# SCH_Weighing-Scale_2024-05-28.net
KiCad netlist of a schematic drawn in EasyEDA
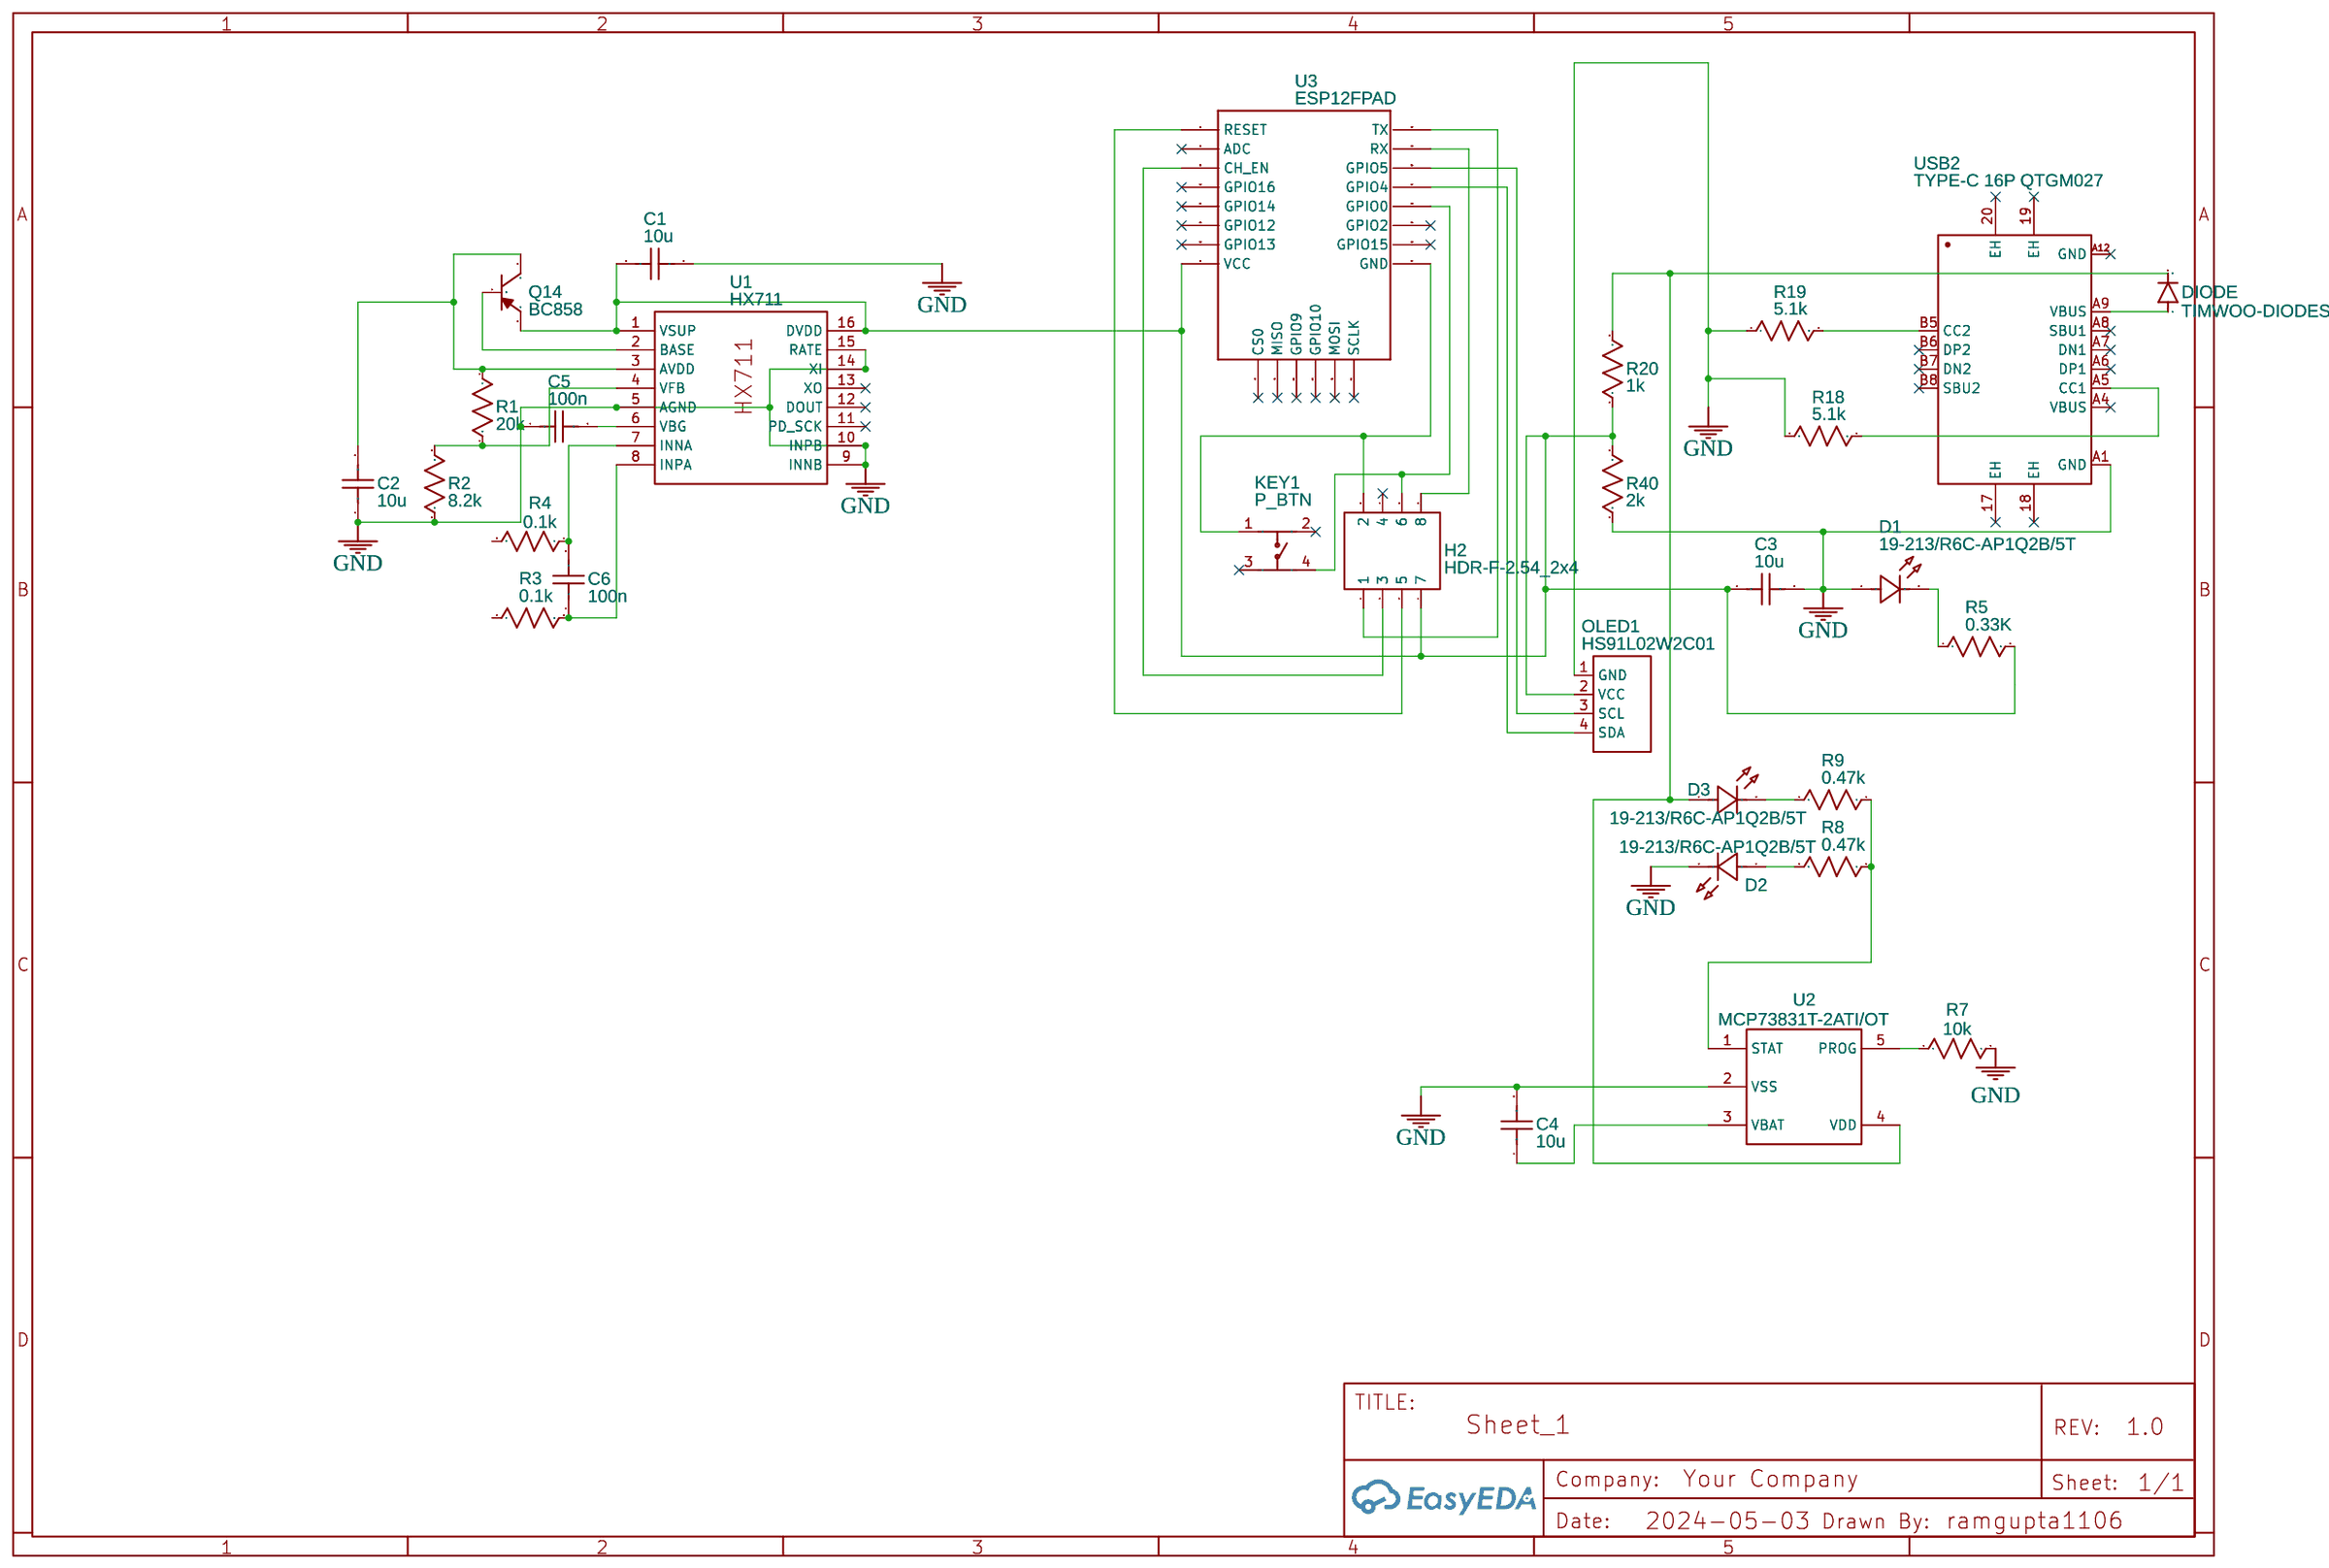
[diagram p0: schematic sheet]

(export (version "E")
  (design (tool "Eeschema 10.0.6"))
  (components
    (comp (ref "C1") (value "10u") (libsource (lib "") (part "C_0603_US_1")))
    (comp (ref "C2") (value "10u") (libsource (lib "") (part "C_0603_US")))
    (comp (ref "C3") (value "10u") (libsource (lib "") (part "C_0603_US_1")))
    (comp (ref "C4") (value "10u") (libsource (lib "") (part "C_0603_US")))
    (comp (ref "C5") (value "100n") (libsource (lib "") (part "C_0603_US_1")))
    (comp (ref "C6") (value "100n") (libsource (lib "") (part "C_0603_US")))
    (comp (ref "D1")
      (value "19-213/R6C-AP1Q2B/5T")
      (fields (field (name "Manufacturer") "EVERLIGHT(亿光)"))
      (libsource (lib "") (part "19-213/R6C-AP1Q2B/5T"))
    )
    (comp (ref "D2")
      (value "19-213/R6C-AP1Q2B/5T")
      (fields (field (name "Manufacturer") "EVERLIGHT(亿光)"))
      (libsource (lib "") (part "19-213/R6C-AP1Q2B/5T_1"))
    )
    (comp (ref "D3")
      (value "19-213/R6C-AP1Q2B/5T")
      (fields (field (name "Manufacturer") "EVERLIGHT(亿光)"))
      (libsource (lib "") (part "19-213/R6C-AP1Q2B/5T"))
    )
    (comp (ref "DIODE") (value "TIMWOO-DIODES_DIODEHV") (libsource (lib "") (part "TIMWOO-DIODES_DIODEHV")))
    (comp (ref "H2") (value "HDR-F-2.54_2x4") (libsource (lib "") (part "HDR-F-2.54_2x4")))
    (comp (ref "KEY1")
      (value "P_BTN")
      (fields (field (name "Manufacturer Part") "4pinTACTPCBTHTPushButton"))
      (libsource (lib "") (part "4PINTACTPCBTHTPUSHBUTTON"))
    )
    (comp (ref "OLED1")
      (value "HS91L02W2C01")
      (fields (field (name "Manufacturer") "HS(汉昇)"))
      (libsource (lib "") (part "HS91L02W2C01"))
    )
    (comp (ref "Q14")
      (value "BC858")
      (fields (field (name "Manufacturer") "HT(Shenzhen Jinyu Semicon)"))
      (libsource (lib "") (part "BC858"))
    )
    (comp (ref "R1") (value "20k") (libsource (lib "") (part "R_0603_US_1")))
    (comp (ref "R2") (value "8.2k") (libsource (lib "") (part "R_0603_US_2")))
    (comp (ref "R3") (value "0.1k") (libsource (lib "") (part "R_0603_US")))
    (comp (ref "R4") (value "0.1k") (libsource (lib "") (part "R_0603_US_3")))
    (comp (ref "R5") (value "0.33K") (libsource (lib "") (part "R_0603_US")))
    (comp (ref "R7") (value "10k") (libsource (lib "") (part "R_0603_US")))
    (comp (ref "R8") (value "0.47k") (libsource (lib "") (part "R_0603_US")))
    (comp (ref "R9") (value "0.47k") (libsource (lib "") (part "R_0603_US")))
    (comp (ref "R18") (value "5.1k") (libsource (lib "") (part "R_0603_US")))
    (comp (ref "R19") (value "5.1k") (libsource (lib "") (part "R_0603_US")))
    (comp (ref "R20") (value "1k") (libsource (lib "") (part "R_0603_US_2")))
    (comp (ref "R40") (value "2k") (libsource (lib "") (part "R_0603_US_2")))
    (comp (ref "U1")
      (value "HX711")
      (fields (field (name "Manufacturer") "AVIA(海芯科技)"))
      (libsource (lib "") (part "HX711"))
    )
    (comp (ref "U2")
      (value "MCP73831T-2ATI/OT")
      (fields (field (name "Manufacturer") "MICROCHIP(美国微芯)"))
      (libsource (lib "") (part "MCP73831T-2ATI/OT"))
    )
    (comp (ref "U3") (value "ESP12FPAD") (libsource (lib "") (part "ESP12FPAD")))
    (comp (ref "USB2")
      (value "TYPE-C 16P QTGM027")
      (fields (field (name "Manufacturer") "SHOU HAN(首韩)"))
      (libsource (lib "") (part "TYPE-C 16P QTGM027"))
    )
  )
  (nets
    (net (code "1") (name "GND") (class "Default")
      (node (ref "C1") (pin "2") (pinfunction "2_2") (pintype "unspecified"))
      (node (ref "C2") (pin "1") (pinfunction "1_1") (pintype "unspecified"))
      (node (ref "C3") (pin "2") (pinfunction "2_2") (pintype "unspecified"))
      (node (ref "C4") (pin "2") (pinfunction "2_2") (pintype "unspecified"))
      (node (ref "C5") (pin "1") (pinfunction "1_1") (pintype "unspecified"))
      (node (ref "D1") (pin "1") (pinfunction "A_1") (pintype "unspecified"))
      (node (ref "D2") (pin "2") (pinfunction "K_2") (pintype "unspecified"))
      (node (ref "OLED1") (pin "1") (pinfunction "GND_1") (pintype "unspecified"))
      (node (ref "R18") (pin "1") (pinfunction "1_1") (pintype "unspecified"))
      (node (ref "R19") (pin "1") (pinfunction "1_1") (pintype "unspecified"))
      (node (ref "R2") (pin "1") (pinfunction "1_1") (pintype "unspecified"))
      (node (ref "R40") (pin "1") (pinfunction "1_1") (pintype "unspecified"))
      (node (ref "R7") (pin "2") (pinfunction "2_2") (pintype "unspecified"))
      (node (ref "U1") (pin "10") (pinfunction "INPB_10") (pintype "unspecified"))
      (node (ref "U1") (pin "14") (pinfunction "XI_14") (pintype "unspecified"))
      (node (ref "U1") (pin "15") (pinfunction "RATE_15") (pintype "unspecified"))
      (node (ref "U1") (pin "5") (pinfunction "AGND_5") (pintype "unspecified"))
      (node (ref "U1") (pin "9") (pinfunction "INNB_9") (pintype "unspecified"))
      (node (ref "U2") (pin "2") (pinfunction "VSS_2") (pintype "unspecified"))
      (node (ref "USB2") (pin "A1") (pinfunction "GND_A1") (pintype "unspecified"))
    )
    (net (code "2") (name "Net-(D1-K)") (class "Default")
      (node (ref "D1") (pin "2") (pinfunction "K_2") (pintype "unspecified"))
      (node (ref "R5") (pin "1") (pinfunction "1_1") (pintype "unspecified"))
    )
    (net (code "3") (name "Net-(D2-A)") (class "Default")
      (node (ref "D2") (pin "1") (pinfunction "A_1") (pintype "unspecified"))
      (node (ref "R8") (pin "1") (pinfunction "1_1") (pintype "unspecified"))
    )
    (net (code "4") (name "Net-(D3-A)") (class "Default")
      (node (ref "D3") (pin "1") (pinfunction "A_1") (pintype "unspecified"))
      (node (ref "DIODE") (pin "C") (pinfunction "C_C") (pintype "bidirectional"))
      (node (ref "R20") (pin "2") (pinfunction "2_2") (pintype "unspecified"))
      (node (ref "U2") (pin "4") (pinfunction "VDD_4") (pintype "unspecified"))
    )
    (net (code "5") (name "Net-(D3-K)") (class "Default")
      (node (ref "D3") (pin "2") (pinfunction "K_2") (pintype "unspecified"))
      (node (ref "R9") (pin "1") (pinfunction "1_1") (pintype "unspecified"))
    )
    (net (code "6") (name "Net-(DIODE-PadA)") (class "Default")
      (node (ref "DIODE") (pin "A") (pinfunction "A_A") (pintype "bidirectional"))
      (node (ref "USB2") (pin "A9") (pinfunction "VBUS_A9") (pintype "unspecified"))
    )
    (net (code "7") (name "Net-(H2-Pad2)") (class "Default")
      (node (ref "H2") (pin "2") (pinfunction "2_2") (pintype "unspecified"))
      (node (ref "KEY1") (pin "1") (pinfunction "1_1") (pintype "unspecified"))
      (node (ref "U3") (pin "GND") (pinfunction "GND_GND") (pintype "bidirectional"))
    )
    (net (code "8") (name "Net-(H2-Pad5)") (class "Default")
      (node (ref "H2") (pin "5") (pinfunction "5_5") (pintype "unspecified"))
      (node (ref "U3") (pin "RESET") (pinfunction "RESET_RESET") (pintype "bidirectional"))
    )
    (net (code "9") (name "Net-(H2-Pad6)") (class "Default")
      (node (ref "H2") (pin "6") (pinfunction "6_6") (pintype "unspecified"))
      (node (ref "KEY1") (pin "4") (pinfunction "4_4") (pintype "unspecified"))
      (node (ref "U3") (pin "GPIO0") (pinfunction "GPIO0_GPIO0") (pintype "bidirectional"))
    )
    (net (code "10") (name "Net-(OLED1-SCL)") (class "Default")
      (node (ref "OLED1") (pin "3") (pinfunction "SCL_3") (pintype "unspecified"))
      (node (ref "U3") (pin "GPIO5") (pinfunction "GPIO5_GPIO5") (pintype "bidirectional"))
    )
    (net (code "11") (name "Net-(OLED1-SDA)") (class "Default")
      (node (ref "OLED1") (pin "4") (pinfunction "SDA_4") (pintype "unspecified"))
      (node (ref "U3") (pin "GPIO4") (pinfunction "GPIO4_GPIO4") (pintype "bidirectional"))
    )
    (net (code "12") (name "Net-(OLED1-VCC)") (class "Default")
      (node (ref "C1") (pin "1") (pinfunction "1_1") (pintype "unspecified"))
      (node (ref "C3") (pin "1") (pinfunction "1_1") (pintype "unspecified"))
      (node (ref "H2") (pin "7") (pinfunction "7_7") (pintype "unspecified"))
      (node (ref "OLED1") (pin "2") (pinfunction "VCC_2") (pintype "unspecified"))
      (node (ref "Q14") (pin "2") (pinfunction "E_2") (pintype "input"))
      (node (ref "R20") (pin "1") (pinfunction "1_1") (pintype "unspecified"))
      (node (ref "R40") (pin "2") (pinfunction "2_2") (pintype "unspecified"))
      (node (ref "R5") (pin "2") (pinfunction "2_2") (pintype "unspecified"))
      (node (ref "U1") (pin "1") (pinfunction "VSUP_1") (pintype "unspecified"))
      (node (ref "U1") (pin "16") (pinfunction "DVDD_16") (pintype "unspecified"))
      (node (ref "U3") (pin "VCC") (pinfunction "VCC_VCC") (pintype "bidirectional"))
    )
    (net (code "13") (name "Net-(Q14-B)") (class "Default")
      (node (ref "Q14") (pin "1") (pinfunction "B_1") (pintype "input"))
      (node (ref "U1") (pin "2") (pinfunction "BASE_2") (pintype "unspecified"))
    )
    (net (code "14") (name "Net-(Q14-C)") (class "Default")
      (node (ref "C2") (pin "2") (pinfunction "2_2") (pintype "unspecified"))
      (node (ref "Q14") (pin "3") (pinfunction "C_3") (pintype "input"))
      (node (ref "R1") (pin "1") (pinfunction "1_1") (pintype "unspecified"))
      (node (ref "U1") (pin "3") (pinfunction "AVDD_3") (pintype "unspecified"))
    )
    (net (code "15") (name "Net-(U1-INNA)") (class "Default")
      (node (ref "C6") (pin "2") (pinfunction "2_2") (pintype "unspecified"))
      (node (ref "R4") (pin "1") (pinfunction "1_1") (pintype "unspecified"))
      (node (ref "U1") (pin "7") (pinfunction "INNA_7") (pintype "unspecified"))
    )
    (net (code "16") (name "Net-(U1-INPA)") (class "Default")
      (node (ref "C6") (pin "1") (pinfunction "1_1") (pintype "unspecified"))
      (node (ref "R3") (pin "2") (pinfunction "2_2") (pintype "unspecified"))
      (node (ref "U1") (pin "8") (pinfunction "INPA_8") (pintype "unspecified"))
    )
    (net (code "17") (name "Net-(U1-VBG)") (class "Default")
      (node (ref "C5") (pin "2") (pinfunction "2_2") (pintype "unspecified"))
      (node (ref "U1") (pin "6") (pinfunction "VBG_6") (pintype "unspecified"))
    )
    (net (code "18") (name "Net-(U1-VFB)") (class "Default")
      (node (ref "R1") (pin "2") (pinfunction "2_2") (pintype "unspecified"))
      (node (ref "R2") (pin "2") (pinfunction "2_2") (pintype "unspecified"))
      (node (ref "U1") (pin "4") (pinfunction "VFB_4") (pintype "unspecified"))
    )
    (net (code "19") (name "Net-(U2-PROG)") (class "Default")
      (node (ref "R7") (pin "1") (pinfunction "1_1") (pintype "unspecified"))
      (node (ref "U2") (pin "5") (pinfunction "PROG_5") (pintype "unspecified"))
    )
    (net (code "20") (name "Net-(U2-STAT)") (class "Default")
      (node (ref "R8") (pin "2") (pinfunction "2_2") (pintype "unspecified"))
      (node (ref "R9") (pin "2") (pinfunction "2_2") (pintype "unspecified"))
      (node (ref "U2") (pin "1") (pinfunction "STAT_1") (pintype "unspecified"))
    )
    (net (code "21") (name "Net-(U2-VBAT)") (class "Default")
      (node (ref "C4") (pin "1") (pinfunction "1_1") (pintype "unspecified"))
      (node (ref "U2") (pin "3") (pinfunction "VBAT_3") (pintype "unspecified"))
    )
    (net (code "22") (name "Net-(U3-CH_EN)") (class "Default")
      (node (ref "H2") (pin "3") (pinfunction "3_3") (pintype "unspecified"))
      (node (ref "U3") (pin "CH_PD") (pinfunction "CH_EN_CH_PD") (pintype "bidirectional"))
    )
    (net (code "23") (name "Net-(U3-RX)") (class "Default")
      (node (ref "H2") (pin "8") (pinfunction "8_8") (pintype "unspecified"))
      (node (ref "U3") (pin "RXD0") (pinfunction "RX_RXD0") (pintype "bidirectional"))
    )
    (net (code "24") (name "Net-(U3-TX)") (class "Default")
      (node (ref "H2") (pin "1") (pinfunction "1_1") (pintype "unspecified"))
      (node (ref "U3") (pin "TXD0") (pinfunction "TX_TXD0") (pintype "bidirectional"))
    )
    (net (code "25") (name "Net-(USB2-CC1)") (class "Default")
      (node (ref "R18") (pin "2") (pinfunction "2_2") (pintype "unspecified"))
      (node (ref "USB2") (pin "A5") (pinfunction "CC1_A5") (pintype "unspecified"))
    )
    (net (code "26") (name "Net-(USB2-CC2)") (class "Default")
      (node (ref "R19") (pin "2") (pinfunction "2_2") (pintype "unspecified"))
      (node (ref "USB2") (pin "B5") (pinfunction "CC2_B5") (pintype "unspecified"))
    )
    (net (code "27") (name "unconnected-(H2-Pad4)") (class "Default")
      (node (ref "H2") (pin "4") (pinfunction "4_4") (pintype "unspecified+no_connect"))
    )
    (net (code "28") (name "unconnected-(KEY1-Pad2)") (class "Default")
      (node (ref "KEY1") (pin "2") (pinfunction "2_2") (pintype "unspecified+no_connect"))
    )
    (net (code "29") (name "unconnected-(KEY1-Pad3)") (class "Default")
      (node (ref "KEY1") (pin "3") (pinfunction "3_3") (pintype "unspecified+no_connect"))
    )
    (net (code "30") (name "unconnected-(R3-Pad1)") (class "Default")
      (node (ref "R3") (pin "1") (pinfunction "1_1") (pintype "unspecified"))
    )
    (net (code "31") (name "unconnected-(R4-Pad2)") (class "Default")
      (node (ref "R4") (pin "2") (pinfunction "2_2") (pintype "unspecified"))
    )
    (net (code "32") (name "unconnected-(U1-DOUT-Pad12)") (class "Default")
      (node (ref "U1") (pin "12") (pinfunction "DOUT_12") (pintype "unspecified+no_connect"))
    )
    (net (code "33") (name "unconnected-(U1-PD_SCK-Pad11)") (class "Default")
      (node (ref "U1") (pin "11") (pinfunction "PD_SCK_11") (pintype "unspecified+no_connect"))
    )
    (net (code "34") (name "unconnected-(U1-XO-Pad13)") (class "Default")
      (node (ref "U1") (pin "13") (pinfunction "XO_13") (pintype "unspecified+no_connect"))
    )
    (net (code "35") (name "unconnected-(U3-PadADC)") (class "Default")
      (node (ref "U3") (pin "ADC") (pinfunction "ADC_ADC") (pintype "bidirectional+no_connect"))
    )
    (net (code "36") (name "unconnected-(U3-PadCS0)") (class "Default")
      (node (ref "U3") (pin "CS0") (pinfunction "CS0_CS0") (pintype "bidirectional+no_connect"))
    )
    (net (code "37") (name "unconnected-(U3-PadGPIO2)") (class "Default")
      (node (ref "U3") (pin "GPIO2") (pinfunction "GPIO2_GPIO2") (pintype "bidirectional+no_connect"))
    )
    (net (code "38") (name "unconnected-(U3-PadGPIO9)") (class "Default")
      (node (ref "U3") (pin "GPIO9") (pinfunction "GPIO9_GPIO9") (pintype "bidirectional+no_connect"))
    )
    (net (code "39") (name "unconnected-(U3-PadGPIO10)") (class "Default")
      (node (ref "U3") (pin "GPIO10") (pinfunction "GPIO10_GPIO10") (pintype "bidirectional+no_connect"))
    )
    (net (code "40") (name "unconnected-(U3-PadGPIO12)") (class "Default")
      (node (ref "U3") (pin "GPIO12") (pinfunction "GPIO12_GPIO12") (pintype "bidirectional+no_connect"))
    )
    (net (code "41") (name "unconnected-(U3-PadGPIO13)") (class "Default")
      (node (ref "U3") (pin "GPIO13") (pinfunction "GPIO13_GPIO13") (pintype "bidirectional+no_connect"))
    )
    (net (code "42") (name "unconnected-(U3-PadGPIO14)") (class "Default")
      (node (ref "U3") (pin "GPIO14") (pinfunction "GPIO14_GPIO14") (pintype "bidirectional+no_connect"))
    )
    (net (code "43") (name "unconnected-(U3-PadGPIO15)") (class "Default")
      (node (ref "U3") (pin "GPIO15") (pinfunction "GPIO15_GPIO15") (pintype "bidirectional+no_connect"))
    )
    (net (code "44") (name "unconnected-(U3-PadGPIO16)") (class "Default")
      (node (ref "U3") (pin "GPIO16") (pinfunction "GPIO16_GPIO16") (pintype "bidirectional+no_connect"))
    )
    (net (code "45") (name "unconnected-(U3-PadMISO)") (class "Default")
      (node (ref "U3") (pin "MISO") (pinfunction "MISO_MISO") (pintype "bidirectional+no_connect"))
    )
    (net (code "46") (name "unconnected-(U3-PadMOSI)") (class "Default")
      (node (ref "U3") (pin "MOSI") (pinfunction "MOSI_MOSI") (pintype "bidirectional+no_connect"))
    )
    (net (code "47") (name "unconnected-(U3-PadSCLK)") (class "Default")
      (node (ref "U3") (pin "SCLK") (pinfunction "SCLK_SCLK") (pintype "bidirectional+no_connect"))
    )
    (net (code "48") (name "unconnected-(USB2-DN1-PadA7)") (class "Default")
      (node (ref "USB2") (pin "A7") (pinfunction "DN1_A7") (pintype "unspecified+no_connect"))
    )
    (net (code "49") (name "unconnected-(USB2-DN2-PadB7)") (class "Default")
      (node (ref "USB2") (pin "B7") (pinfunction "DN2_B7") (pintype "unspecified+no_connect"))
    )
    (net (code "50") (name "unconnected-(USB2-DP1-PadA6)") (class "Default")
      (node (ref "USB2") (pin "A6") (pinfunction "DP1_A6") (pintype "unspecified+no_connect"))
    )
    (net (code "51") (name "unconnected-(USB2-DP2-PadB6)") (class "Default")
      (node (ref "USB2") (pin "B6") (pinfunction "DP2_B6") (pintype "unspecified+no_connect"))
    )
    (net (code "52") (name "unconnected-(USB2-EH-Pad17)") (class "Default")
      (node (ref "USB2") (pin "17") (pinfunction "EH_17") (pintype "unspecified+no_connect"))
    )
    (net (code "53") (name "unconnected-(USB2-EH-Pad18)") (class "Default")
      (node (ref "USB2") (pin "18") (pinfunction "EH_18") (pintype "unspecified+no_connect"))
    )
    (net (code "54") (name "unconnected-(USB2-EH-Pad19)") (class "Default")
      (node (ref "USB2") (pin "19") (pinfunction "EH_19") (pintype "unspecified+no_connect"))
    )
    (net (code "55") (name "unconnected-(USB2-EH-Pad20)") (class "Default")
      (node (ref "USB2") (pin "20") (pinfunction "EH_20") (pintype "unspecified+no_connect"))
    )
    (net (code "56") (name "unconnected-(USB2-GND-PadA12)") (class "Default")
      (node (ref "USB2") (pin "A12") (pinfunction "GND_A12") (pintype "unspecified+no_connect"))
    )
    (net (code "57") (name "unconnected-(USB2-SBU1-PadA8)") (class "Default")
      (node (ref "USB2") (pin "A8") (pinfunction "SBU1_A8") (pintype "unspecified+no_connect"))
    )
    (net (code "58") (name "unconnected-(USB2-SBU2-PadB8)") (class "Default")
      (node (ref "USB2") (pin "B8") (pinfunction "SBU2_B8") (pintype "unspecified+no_connect"))
    )
    (net (code "59") (name "unconnected-(USB2-VBUS-PadA4)") (class "Default")
      (node (ref "USB2") (pin "A4") (pinfunction "VBUS_A4") (pintype "unspecified+no_connect"))
    )
  )
)
